# TestPoints.net
KiCad netlist of a schematic drawn in Altium Designer
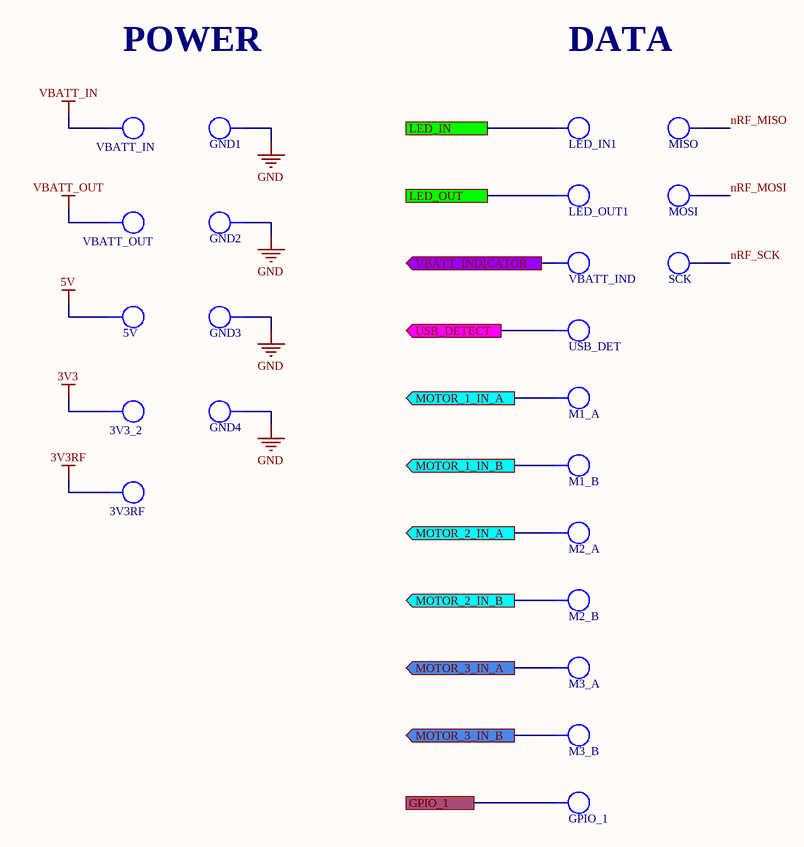
[diagram p0: TestPoints.SchDoc]

(export (version "E")
  (design (tool "Eeschema 10.0.6"))
  (components
    (comp (ref "3V3RF")
      (value "TP")
      (footprint "TP_1206")
      (description "Test-Point 3.3x1.6x2.1mm SMD")
      (fields
        (field (name "MANUFACTURER") "Harwin Inc")
        (field (name "MANUFACTURER PART NUMBER") "S1751-46R")
      )
      (libsource (lib "ECE AD19Components_19V1") (part "TP_1206"))
    )
    (comp (ref "3V3_2")
      (value "TP")
      (footprint "TP_1206")
      (description "Test-Point 3.3x1.6x2.1mm SMD")
      (fields
        (field (name "MANUFACTURER") "Harwin Inc")
        (field (name "MANUFACTURER PART NUMBER") "S1751-46R")
      )
      (libsource (lib "ECE AD19Components_19V1") (part "TP_1206"))
    )
    (comp (ref "5V")
      (value "TP")
      (footprint "TP_1206")
      (description "Test-Point 3.3x1.6x2.1mm SMD")
      (fields
        (field (name "MANUFACTURER") "Harwin Inc")
        (field (name "MANUFACTURER PART NUMBER") "S1751-46R")
      )
      (libsource (lib "ECE AD19Components_19V1") (part "TP_1206"))
    )
    (comp (ref "GND1")
      (value "TP")
      (footprint "TP_1206")
      (description "Test-Point 3.3x1.6x2.1mm SMD")
      (fields
        (field (name "MANUFACTURER") "Harwin Inc")
        (field (name "MANUFACTURER PART NUMBER") "S1751-46R")
      )
      (libsource (lib "ECE AD19Components_19V1") (part "TP_1206"))
    )
    (comp (ref "GND2")
      (value "TP")
      (footprint "TP_1206")
      (description "Test-Point 3.3x1.6x2.1mm SMD")
      (fields
        (field (name "MANUFACTURER") "Harwin Inc")
        (field (name "MANUFACTURER PART NUMBER") "S1751-46R")
      )
      (libsource (lib "ECE AD19Components_19V1") (part "TP_1206"))
    )
    (comp (ref "GND3")
      (value "TP")
      (footprint "TP_1206")
      (description "Test-Point 3.3x1.6x2.1mm SMD")
      (fields
        (field (name "MANUFACTURER") "Harwin Inc")
        (field (name "MANUFACTURER PART NUMBER") "S1751-46R")
      )
      (libsource (lib "ECE AD19Components_19V1") (part "TP_1206"))
    )
    (comp (ref "GND4")
      (value "TP")
      (footprint "TP_1206")
      (description "Test-Point 3.3x1.6x2.1mm SMD")
      (fields
        (field (name "MANUFACTURER") "Harwin Inc")
        (field (name "MANUFACTURER PART NUMBER") "S1751-46R")
      )
      (libsource (lib "ECE AD19Components_19V1") (part "TP_1206"))
    )
    (comp (ref "GPIO_1")
      (value "TP")
      (footprint "TP_1206")
      (description "Test-Point 3.3x1.6x2.1mm SMD")
      (fields
        (field (name "MANUFACTURER") "Harwin Inc")
        (field (name "MANUFACTURER PART NUMBER") "S1751-46R")
      )
      (libsource (lib "ECE AD19Components_19V1") (part "TP_1206"))
    )
    (comp (ref "LED_IN1")
      (value "~")
      (footprint "TP_0603")
      (description "Test Point 1.65X0.9X1.2mm SMD")
      (fields
        (field (name "MANUFACTURER") "TE Connectivity AMP Connectors")
        (field (name "MANUFACTURER PART NUMBER") "1625854-3")
      )
      (libsource (lib "ECE AD19Components_19V1") (part "TP_0603"))
    )
    (comp (ref "LED_OUT1")
      (value "TP")
      (footprint "TP_1206")
      (description "Test-Point 3.3x1.6x2.1mm SMD")
      (fields
        (field (name "MANUFACTURER") "Harwin Inc")
        (field (name "MANUFACTURER PART NUMBER") "S1751-46R")
      )
      (libsource (lib "ECE AD19Components_19V1") (part "TP_1206"))
    )
    (comp (ref "M1_A")
      (value "TP")
      (footprint "TP_1206")
      (description "Test-Point 3.3x1.6x2.1mm SMD")
      (fields
        (field (name "MANUFACTURER") "Harwin Inc")
        (field (name "MANUFACTURER PART NUMBER") "S1751-46R")
      )
      (libsource (lib "ECE AD19Components_19V1") (part "TP_1206"))
    )
    (comp (ref "M1_B")
      (value "TP")
      (footprint "TP_1206")
      (description "Test-Point 3.3x1.6x2.1mm SMD")
      (fields
        (field (name "MANUFACTURER") "Harwin Inc")
        (field (name "MANUFACTURER PART NUMBER") "S1751-46R")
      )
      (libsource (lib "ECE AD19Components_19V1") (part "TP_1206"))
    )
    (comp (ref "M2_A")
      (value "TP")
      (footprint "TP_1206")
      (description "Test-Point 3.3x1.6x2.1mm SMD")
      (fields
        (field (name "MANUFACTURER") "Harwin Inc")
        (field (name "MANUFACTURER PART NUMBER") "S1751-46R")
      )
      (libsource (lib "ECE AD19Components_19V1") (part "TP_1206"))
    )
    (comp (ref "M2_B")
      (value "TP")
      (footprint "TP_1206")
      (description "Test-Point 3.3x1.6x2.1mm SMD")
      (fields
        (field (name "MANUFACTURER") "Harwin Inc")
        (field (name "MANUFACTURER PART NUMBER") "S1751-46R")
      )
      (libsource (lib "ECE AD19Components_19V1") (part "TP_1206"))
    )
    (comp (ref "M3_A")
      (value "TP")
      (footprint "TP_1206")
      (description "Test-Point 3.3x1.6x2.1mm SMD")
      (fields
        (field (name "MANUFACTURER") "Harwin Inc")
        (field (name "MANUFACTURER PART NUMBER") "S1751-46R")
      )
      (libsource (lib "ECE AD19Components_19V1") (part "TP_1206"))
    )
    (comp (ref "M3_B")
      (value "TP")
      (footprint "TP_1206")
      (description "Test-Point 3.3x1.6x2.1mm SMD")
      (fields
        (field (name "MANUFACTURER") "Harwin Inc")
        (field (name "MANUFACTURER PART NUMBER") "S1751-46R")
      )
      (libsource (lib "ECE AD19Components_19V1") (part "TP_1206"))
    )
    (comp (ref "MISO")
      (value "TP_0603")
      (footprint "TP_0603")
      (description "Test Point 1.65X0.9X1.2mm SMD")
      (fields
        (field (name "MANUFACTURER") "TE Connectivity AMP Connectors")
        (field (name "MANUFACTURER PART NUMBER") "1625854-3")
      )
      (libsource (lib "ECE AD19Components_19V1") (part "TP_0603"))
    )
    (comp (ref "MOSI")
      (value "~")
      (footprint "TP_0603")
      (description "Test Point 1.65X0.9X1.2mm SMD")
      (fields
        (field (name "MANUFACTURER") "TE Connectivity AMP Connectors")
        (field (name "MANUFACTURER PART NUMBER") "1625854-3")
      )
      (libsource (lib "ECE AD19Components_19V1") (part "TP_0603"))
    )
    (comp (ref "SCK")
      (value "~")
      (footprint "TP_0603")
      (description "Test Point 1.65X0.9X1.2mm SMD")
      (fields
        (field (name "MANUFACTURER") "TE Connectivity AMP Connectors")
        (field (name "MANUFACTURER PART NUMBER") "1625854-3")
      )
      (libsource (lib "ECE AD19Components_19V1") (part "TP_0603"))
    )
    (comp (ref "USB_DET")
      (value "TP")
      (footprint "TP_1206")
      (description "Test-Point 3.3x1.6x2.1mm SMD")
      (fields
        (field (name "MANUFACTURER") "Harwin Inc")
        (field (name "MANUFACTURER PART NUMBER") "S1751-46R")
      )
      (libsource (lib "ECE AD19Components_19V1") (part "TP_1206"))
    )
    (comp (ref "VBATT_IN")
      (value "TP")
      (footprint "TP_1206")
      (description "Test-Point 3.3x1.6x2.1mm SMD")
      (fields
        (field (name "MANUFACTURER") "Harwin Inc")
        (field (name "MANUFACTURER PART NUMBER") "S1751-46R")
      )
      (libsource (lib "ECE AD19Components_19V1") (part "TP_1206"))
    )
    (comp (ref "VBATT_IND")
      (value "TP")
      (footprint "TP_1206")
      (description "Test-Point 3.3x1.6x2.1mm SMD")
      (fields
        (field (name "MANUFACTURER") "Harwin Inc")
        (field (name "MANUFACTURER PART NUMBER") "S1751-46R")
      )
      (libsource (lib "ECE AD19Components_19V1") (part "TP_1206"))
    )
    (comp (ref "VBATT_OUT")
      (value "TP")
      (footprint "TP_1206")
      (description "Test-Point 3.3x1.6x2.1mm SMD")
      (fields
        (field (name "MANUFACTURER") "Harwin Inc")
        (field (name "MANUFACTURER PART NUMBER") "S1751-46R")
      )
      (libsource (lib "ECE AD19Components_19V1") (part "TP_1206"))
    )
  )
  (nets
    (net (code "1") (name "/GPIO_1") (class "Default")
      (node (ref "GPIO_1") (pin "1") (pinfunction "1_1") (pintype "passive"))
    )
    (net (code "2") (name "/LED_IN") (class "Default")
      (node (ref "LED_IN1") (pin "1") (pinfunction "TP_1") (pintype "passive"))
    )
    (net (code "3") (name "/LED_OUT") (class "Default")
      (node (ref "LED_OUT1") (pin "1") (pinfunction "1_1") (pintype "passive"))
    )
    (net (code "4") (name "/MOTOR_1_IN_A") (class "Default")
      (node (ref "M1_A") (pin "1") (pinfunction "1_1") (pintype "passive"))
    )
    (net (code "5") (name "/MOTOR_1_IN_B") (class "Default")
      (node (ref "M1_B") (pin "1") (pinfunction "1_1") (pintype "passive"))
    )
    (net (code "6") (name "/MOTOR_2_IN_A") (class "Default")
      (node (ref "M2_A") (pin "1") (pinfunction "1_1") (pintype "passive"))
    )
    (net (code "7") (name "/MOTOR_2_IN_B") (class "Default")
      (node (ref "M2_B") (pin "1") (pinfunction "1_1") (pintype "passive"))
    )
    (net (code "8") (name "/MOTOR_3_IN_A") (class "Default")
      (node (ref "M3_A") (pin "1") (pinfunction "1_1") (pintype "passive"))
    )
    (net (code "9") (name "/MOTOR_3_IN_B") (class "Default")
      (node (ref "M3_B") (pin "1") (pinfunction "1_1") (pintype "passive"))
    )
    (net (code "10") (name "/USB_DETECT") (class "Default")
      (node (ref "USB_DET") (pin "1") (pinfunction "1_1") (pintype "passive"))
    )
    (net (code "11") (name "/VBATT_INDICATOR") (class "Default")
      (node (ref "VBATT_IND") (pin "1") (pinfunction "1_1") (pintype "passive"))
    )
    (net (code "12") (name "/nRF_MISO") (class "Default")
      (node (ref "MISO") (pin "1") (pinfunction "TP_1") (pintype "passive"))
    )
    (net (code "13") (name "/nRF_MOSI") (class "Default")
      (node (ref "MOSI") (pin "1") (pinfunction "TP_1") (pintype "passive"))
    )
    (net (code "14") (name "/nRF_SCK") (class "Default")
      (node (ref "SCK") (pin "1") (pinfunction "TP_1") (pintype "passive"))
    )
    (net (code "15") (name "3V3") (class "Default")
      (node (ref "3V3_2") (pin "1") (pinfunction "1_1") (pintype "passive"))
    )
    (net (code "16") (name "3V3RF") (class "Default")
      (node (ref "3V3RF") (pin "1") (pinfunction "1_1") (pintype "passive"))
    )
    (net (code "17") (name "5V") (class "Default")
      (node (ref "5V") (pin "1") (pinfunction "1_1") (pintype "passive"))
    )
    (net (code "18") (name "GND") (class "Default")
      (node (ref "GND1") (pin "1") (pinfunction "1_1") (pintype "passive"))
      (node (ref "GND2") (pin "1") (pinfunction "1_1") (pintype "passive"))
      (node (ref "GND3") (pin "1") (pinfunction "1_1") (pintype "passive"))
      (node (ref "GND4") (pin "1") (pinfunction "1_1") (pintype "passive"))
    )
    (net (code "19") (name "VBATT_IN") (class "Default")
      (node (ref "VBATT_IN") (pin "1") (pinfunction "1_1") (pintype "passive"))
    )
    (net (code "20") (name "VBATT_OUT") (class "Default")
      (node (ref "VBATT_OUT") (pin "1") (pinfunction "1_1") (pintype "passive"))
    )
  )
)
